# RTC.net
KiCad netlist of a schematic drawn in Altium Designer
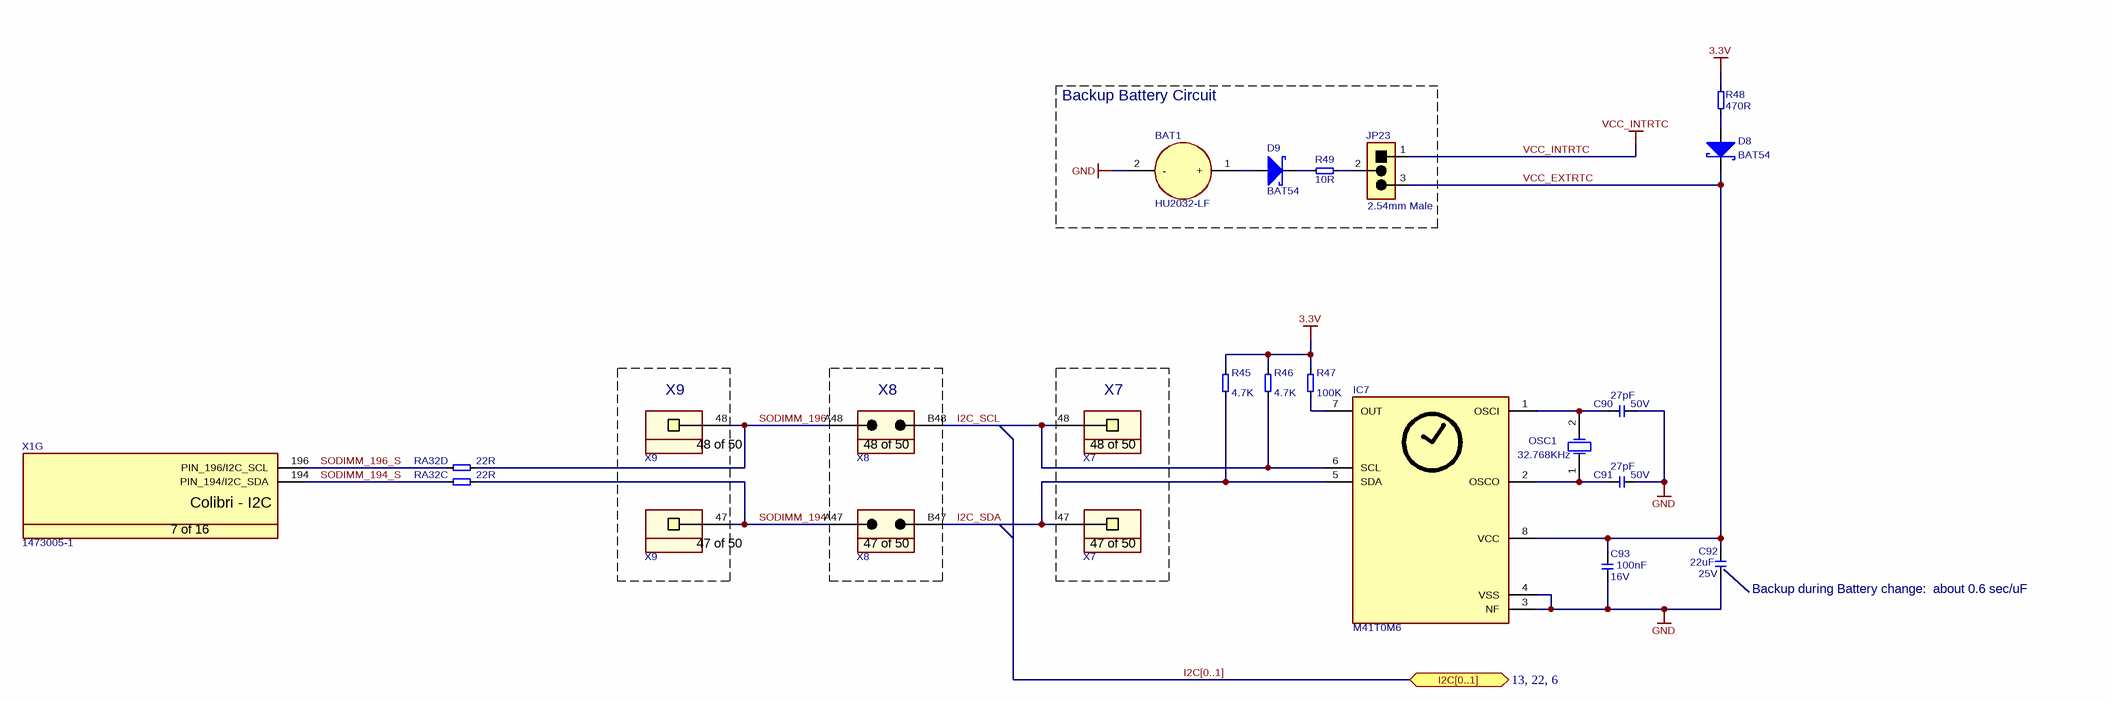
[diagram p0: RTC.SchDoc]

(export (version "E")
  (design (tool "Eeschema 10.0.6"))
  (components
    (comp (ref "BAT1")
      (value "HU2032-LF")
      (footprint "T_Renata_HU2032-LF")
      (description "C2032 Battery Holder")
      (fields (field (name "MANUFACTURER PART NO.") "HU2032-LF"))
      (libsource (lib "Evaluation Board") (part "BAT-Renata-HU2032-LF"))
    )
    (comp (ref "C90")
      (value "27pF")
      (footprint "T_CAPC0603X33N")
      (description "Capacitor Ceramic NPO 27pF 50V 5% 0603")
      (fields (field (name "TOLERANCE") "5%") (field (name "RATING") "50V"))
      (libsource (lib "Evaluation Board") (part "C-NPO-27pF-50V-5%-0603"))
    )
    (comp (ref "C91")
      (value "27pF")
      (footprint "T_CAPC0603X33N")
      (description "Capacitor Ceramic NPO 27pF 50V 5% 0603")
      (fields (field (name "TOLERANCE") "5%") (field (name "RATING") "50V"))
      (libsource (lib "Evaluation Board") (part "C-NPO-27pF-50V-5%-0603"))
    )
    (comp (ref "C92")
      (value "22uF")
      (footprint "CAPC3225X160N")
      (description "Capacitor Ceramic X5R 22uF 25V 20% 1210")
      (fields (field (name "TOLERANCE") "20%") (field (name "RATING") "25V"))
      (libsource (lib "Evaluation Board") (part "C-X5R-22uF-25V-20%-1210"))
    )
    (comp (ref "C93")
      (value "100nF")
      (footprint "T_CAPC0603X33N")
      (description "Capacitor Ceramic X7R 100nF 16V 10% 0603")
      (fields (field (name "TOLERANCE") "10%") (field (name "RATING") "16V"))
      (libsource (lib "Evaluation Board") (part "C-X7R-100nF-16V-10%-0603"))
    )
    (comp (ref "D8")
      (value "BAT54")
      (footprint "SOT95P230X110-3N")
      (description "BAT54 Schottky Diode")
      (fields (field (name "MANUFACTURER PART NO.") "BAT54"))
      (libsource (lib "Evaluation Board") (part "D-Philips-BAT54-Schottky"))
    )
    (comp (ref "D9")
      (value "BAT54")
      (footprint "SOT95P230X110-3N")
      (description "BAT54 Schottky Diode")
      (fields (field (name "MANUFACTURER PART NO.") "BAT54"))
      (libsource (lib "Evaluation Board") (part "D-Philips-BAT54-Schottky"))
    )
    (comp (ref "IC7")
      (value "M41T0M6")
      (footprint "SOIC127P600X173-8N")
      (description "RTC M41T0M6")
      (fields (field (name "MANUFACTURER PART NO.") "M41T0M6"))
      (libsource (lib "Evaluation Board") (part "IC-ST-M41T0M6"))
    )
    (comp (ref "JP23")
      (value "826936-3")
      (footprint "T_TYCO_826936-3")
      (description "Jumper, 3-Pin")
      (libsource (lib "Evaluation Board") (part "CON-Tyco-826936-3-1X3-2.54mm-JP_1"))
    )
    (comp (ref "OSC1")
      (value "32.768KHz")
      (footprint "T_MC_CC4V-T1A")
      (description "Quartz 32.768kHz")
      (fields (field (name "TOLERANCE") "30ppm") (field (name "MANUFACTURER PART NO.") "CC4V-T1A"))
      (libsource (lib "Evaluation Board") (part "OSC-MC-CC4V-T1A-32.768KHz-30ppm-5x1.9mm"))
    )
    (comp (ref "R45")
      (value "4.7K")
      (footprint "t_RESC0603X30N")
      (description "Resistor 4.7 Kohm 63mW 5% 0603")
      (fields (field (name "TOLERANCE") "5%"))
      (libsource (lib "Evaluation Board") (part "R-4.7kR-63mW-5%-0603"))
    )
    (comp (ref "R46")
      (value "4.7K")
      (footprint "t_RESC0603X30N")
      (description "Resistor 4.7 Kohm 63mW 5% 0603")
      (fields (field (name "TOLERANCE") "5%"))
      (libsource (lib "Evaluation Board") (part "R-4.7kR-63mW-5%-0603"))
    )
    (comp (ref "R47")
      (value "100K")
      (footprint "t_RESC0603X30N")
      (description "Resistor 100 Kohm 63mW 5% 0603")
      (fields (field (name "TOLERANCE") "5%"))
      (libsource (lib "Evaluation Board") (part "R-100KR-63mW-5%-0603"))
    )
    (comp (ref "R48")
      (value "470R")
      (footprint "T_RESC0603X30N")
      (description "Resistor 470 ohm 63mW 5% 0603")
      (fields (field (name "TOLERANCE") "5%"))
      (libsource (lib "Evaluation Board") (part "R-470R-63mW-5%-0603"))
    )
    (comp (ref "R49")
      (value "10R")
      (footprint "t_RESC0603X30N")
      (description "Resistor 10 ohm 63mW 5% 0603")
      (fields (field (name "TOLERANCE") "5%"))
      (libsource (lib "Evaluation Board") (part "R-10R-63mW-5%-0603"))
    )
    (comp (ref "RA32")
      (value "22R")
      (footprint "T_Resistor_Array_X4")
      (description "Resistor Array 22 R 63mW 5% 1206")
      (fields (field (name "TOLERANCE") "5%"))
      (libsource (lib "Evaluation Board") (part "RA-22R-63mW-5%-1206-div"))
    )
    (comp (ref "X1")
      (value "CON-Tyco-1473005-1-200-0.6mm")
      (footprint "T_Tyco_1473005-1")
      (description "SODIMM Connector")
      (fields (field (name "MANUFACTURER PART NO.") "1473005-1"))
      (libsource (lib "Evaluation Board") (part "CON-Tyco-1473005-1-200-0.6mm"))
    )
    (comp (ref "X7")
      (value "SSW-110-01-G-S")
      (footprint "T_Samtec_SSW-110-01-G-S")
      (description "Header 1x50 pin 2.54mm pitch")
      (libsource (lib "") (part "CON-Samtec-SSW-110-01-G-S_1"))
    )
    (comp (ref "X8")
      (value "TSW-110-07-G-D")
      (footprint "T_Samtec_TSW-110-07-G-D")
      (description "Header 2x50 pin 2.54mm pitch")
      (libsource (lib "Evaluation Board") (part "CON-Samtec-TSW-110-07-G-D"))
    )
    (comp (ref "X9")
      (value "SSW-110-01-G-S")
      (footprint "T_Samtec_SSW-110-01-G-S")
      (description "Header 1x50 pin 2.54mm pitch")
      (libsource (lib "Evaluation Board") (part "CON-Samtec-SSW-110-01-G-S"))
    )
  )
  (nets
    (net (code "4") (name "/I2C_SCL") (class "Default")
      (node (ref "IC7") (pin "6") (pinfunction "SCL_6") (pintype "passive"))
      (node (ref "R46") (pin "1") (pinfunction "1_1") (pintype "passive"))
      (node (ref "X7") (pin "48") (pinfunction "48_48") (pintype "passive"))
      (node (ref "X8") (pin "B48") (pinfunction "B48_B48") (pintype "passive"))
    )
    (net (code "5") (name "/I2C_SDA") (class "Default")
      (node (ref "IC7") (pin "5") (pinfunction "SDA_5") (pintype "passive"))
      (node (ref "R45") (pin "1") (pinfunction "1_1") (pintype "passive"))
      (node (ref "X7") (pin "47") (pinfunction "47_47") (pintype "passive"))
      (node (ref "X8") (pin "B47") (pinfunction "B47_B47") (pintype "passive"))
    )
    (net (code "6") (name "/SODIMM_194") (class "Default")
      (node (ref "RA32") (pin "7") (pinfunction "7_7") (pintype "passive"))
      (node (ref "X8") (pin "A47") (pinfunction "A47_A47") (pintype "passive"))
      (node (ref "X9") (pin "47") (pinfunction "47_47") (pintype "passive"))
    )
    (net (code "7") (name "/SODIMM_194_S") (class "Default")
      (node (ref "RA32") (pin "3") (pinfunction "3_3") (pintype "passive"))
      (node (ref "X1") (pin "194") (pinfunction "PIN_194/I2C_SDA_194") (pintype "passive"))
    )
    (net (code "8") (name "/SODIMM_196") (class "Default")
      (node (ref "RA32") (pin "8") (pinfunction "8_8") (pintype "passive"))
      (node (ref "X8") (pin "A48") (pinfunction "A48_A48") (pintype "passive"))
      (node (ref "X9") (pin "48") (pinfunction "48_48") (pintype "passive"))
    )
    (net (code "9") (name "/SODIMM_196_S") (class "Default")
      (node (ref "RA32") (pin "4") (pinfunction "4_4") (pintype "passive"))
      (node (ref "X1") (pin "196") (pinfunction "PIN_196/I2C_SCL_196") (pintype "passive"))
    )
    (net (code "10") (name "/VCC_EXTRTC") (class "Default")
      (node (ref "C92") (pin "2") (pinfunction "2_2") (pintype "passive"))
      (node (ref "C93") (pin "2") (pinfunction "2_2") (pintype "passive"))
      (node (ref "D8") (pin "3") (pinfunction "3_3") (pintype "passive"))
      (node (ref "IC7") (pin "8") (pinfunction "VCC_8") (pintype "passive"))
      (node (ref "JP23") (pin "3") (pinfunction "3_3") (pintype "passive"))
    )
    (net (code "11") (name "3.3V") (class "Default")
      (node (ref "R45") (pin "2") (pinfunction "2_2") (pintype "passive"))
      (node (ref "R46") (pin "2") (pinfunction "2_2") (pintype "passive"))
      (node (ref "R47") (pin "2") (pinfunction "2_2") (pintype "passive"))
      (node (ref "R48") (pin "2") (pinfunction "2_2") (pintype "passive"))
    )
    (net (code "12") (name "GND") (class "Default")
      (node (ref "BAT1") (pin "2") (pinfunction "-_2") (pintype "passive"))
      (node (ref "C90") (pin "2") (pinfunction "2_2") (pintype "passive"))
      (node (ref "C91") (pin "2") (pinfunction "2_2") (pintype "passive"))
      (node (ref "C92") (pin "1") (pinfunction "1_1") (pintype "passive"))
      (node (ref "C93") (pin "1") (pinfunction "1_1") (pintype "passive"))
      (node (ref "IC7") (pin "3") (pinfunction "NF_3") (pintype "passive"))
      (node (ref "IC7") (pin "4") (pinfunction "VSS_4") (pintype "passive"))
    )
    (net (code "13") (name "Net-(BAT1-+)") (class "Default")
      (node (ref "BAT1") (pin "1") (pinfunction "+_1") (pintype "passive"))
      (node (ref "D9") (pin "1") (pinfunction "1_1") (pintype "passive"))
    )
    (net (code "14") (name "Net-(D8-Pad1)") (class "Default")
      (node (ref "D8") (pin "1") (pinfunction "1_1") (pintype "passive"))
      (node (ref "R48") (pin "1") (pinfunction "1_1") (pintype "passive"))
    )
    (net (code "15") (name "Net-(D9-Pad3)") (class "Default")
      (node (ref "D9") (pin "3") (pinfunction "3_3") (pintype "passive"))
      (node (ref "R49") (pin "1") (pinfunction "1_1") (pintype "passive"))
    )
    (net (code "16") (name "Net-(IC7-OSCI)") (class "Default")
      (node (ref "C90") (pin "1") (pinfunction "1_1") (pintype "passive"))
      (node (ref "IC7") (pin "1") (pinfunction "OSCI_1") (pintype "passive"))
      (node (ref "OSC1") (pin "2") (pinfunction "OSC2_2") (pintype "passive"))
    )
    (net (code "17") (name "Net-(IC7-OSCO)") (class "Default")
      (node (ref "C91") (pin "1") (pinfunction "1_1") (pintype "passive"))
      (node (ref "IC7") (pin "2") (pinfunction "OSCO_2") (pintype "passive"))
      (node (ref "OSC1") (pin "1") (pinfunction "OSC1_1") (pintype "passive"))
    )
    (net (code "18") (name "Net-(IC7-OUT)") (class "Default")
      (node (ref "IC7") (pin "7") (pinfunction "OUT_7") (pintype "passive"))
      (node (ref "R47") (pin "1") (pinfunction "1_1") (pintype "passive"))
    )
    (net (code "19") (name "Net-(JP23-Pad2)") (class "Default")
      (node (ref "JP23") (pin "2") (pinfunction "2_2") (pintype "passive"))
      (node (ref "R49") (pin "2") (pinfunction "2_2") (pintype "passive"))
    )
    (net (code "20") (name "VCC_INTRTC") (class "Default")
      (node (ref "JP23") (pin "1") (pinfunction "1_1") (pintype "passive"))
    )
  )
)
